# SCH_starseven_2025-07-26.net
KiCad netlist of a schematic drawn in EasyEDA
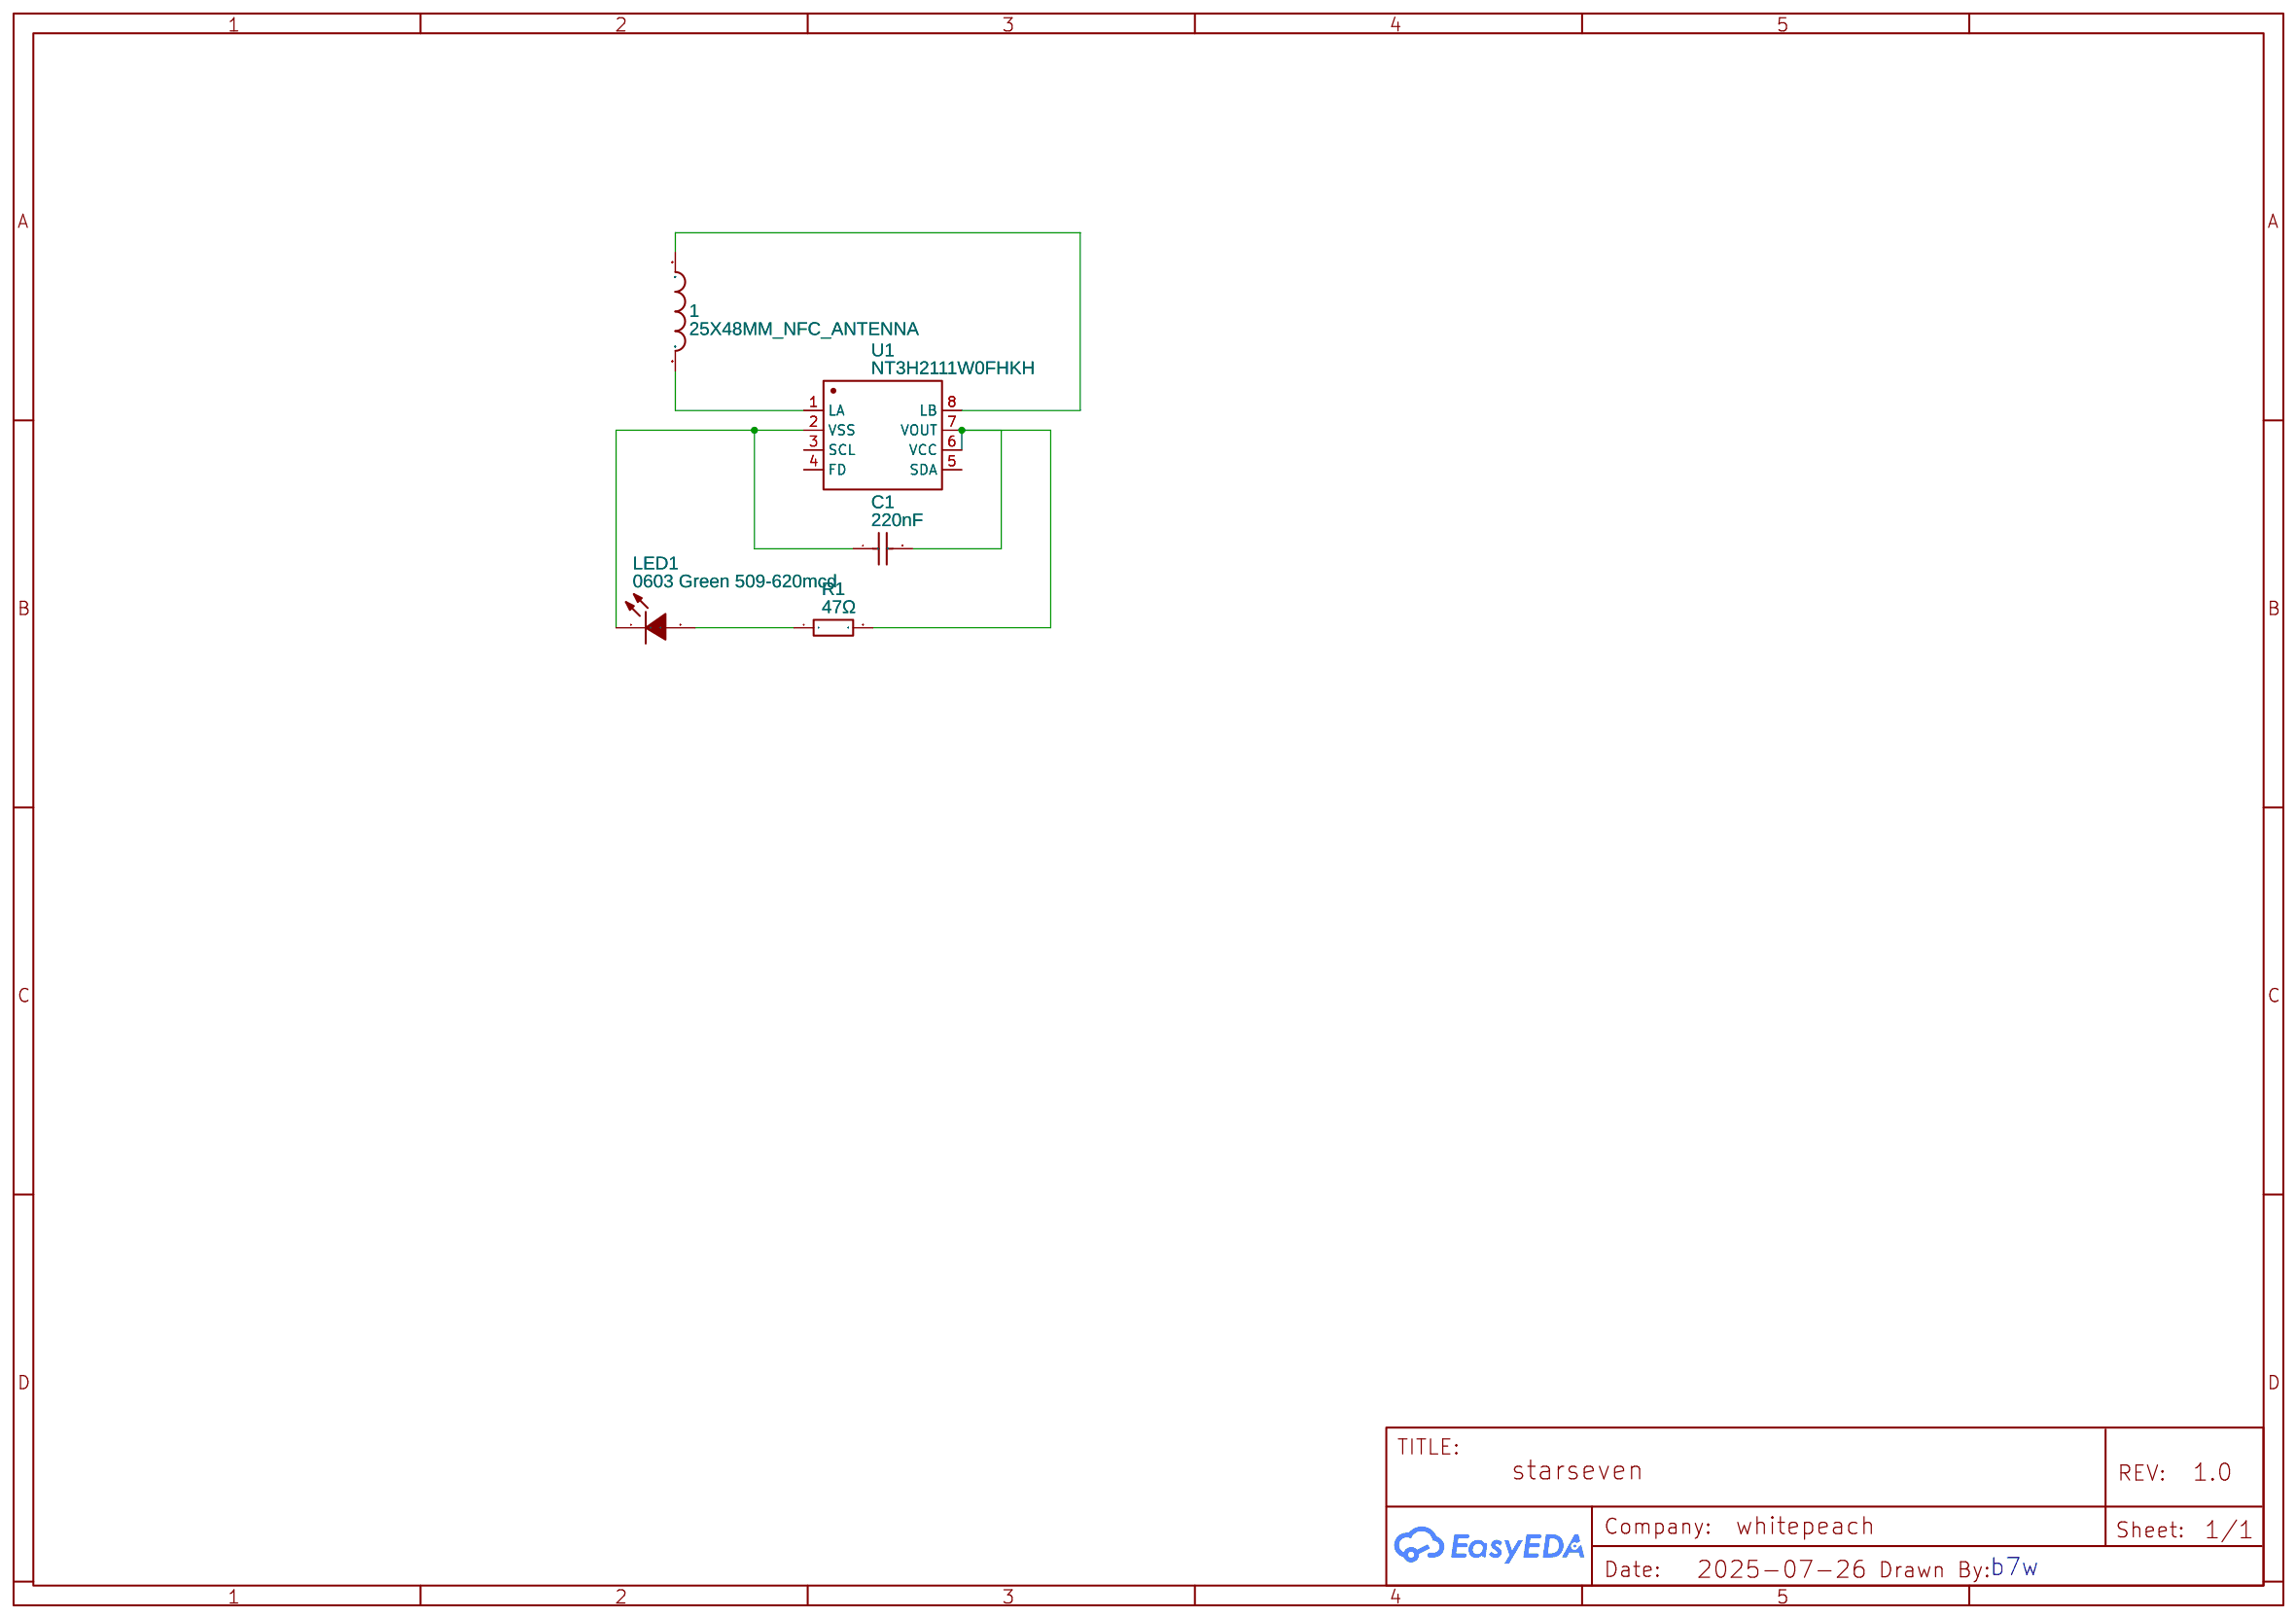
[diagram p0: schematic sheet]

(export (version "E")
  (design (tool "Eeschema 10.0.6"))
  (components
    (comp (ref "1") (value "25X48MM_NFC_ANTENNA") (libsource (lib "") (part "25X48MM_NFC_ANTENNA")))
    (comp (ref "C1")
      (value "220nF")
      (fields
        (field (name "Manufacturer Part") "CL10B224KA8NNNC")
        (field (name "Manufacturer") "SAMSUNG(三星)")
      )
      (libsource (lib "") (part "CL10B224KA8NNNC"))
    )
    (comp (ref "LED1")
      (value "0603 Green 509-620mcd")
      (fields (field (name "Manufacturer Part") "KT-0603G") (field (name "Manufacturer") "KENTO"))
      (libsource (lib "") (part "0603 Green 509-620mcd"))
    )
    (comp (ref "R1")
      (value "47Ω")
      (fields
        (field (name "Manufacturer Part") "0603WAF470JT5E")
        (field (name "Manufacturer") "UNI-ROYAL(厚声)")
      )
      (libsource (lib "") (part "0603WAF470JT5E"))
    )
    (comp (ref "U1")
      (value "NT3H2111W0FHKH")
      (fields (field (name "Manufacturer") "NXP(恩智浦)"))
      (libsource (lib "") (part "NT3H2111W0FHKH"))
    )
  )
  (nets
    (net (code "1") (name "Net-(LED1-A)") (class "Default")
      (node (ref "LED1") (pin "2") (pinfunction "A_2") (pintype "unspecified"))
      (node (ref "R1") (pin "1") (pinfunction "1_1") (pintype "input"))
    )
    (net (code "2") (name "Net-(LED1-K)") (class "Default")
      (node (ref "C1") (pin "1") (pinfunction "1_1") (pintype "input"))
      (node (ref "LED1") (pin "1") (pinfunction "K_1") (pintype "unspecified"))
      (node (ref "U1") (pin "2") (pinfunction "VSS_2") (pintype "unspecified"))
    )
    (net (code "3") (name "Net-(U1-LA)") (class "Default")
      (node (ref "1") (pin "P$2") (pinfunction "P$2_P$2") (pintype "bidirectional"))
      (node (ref "U1") (pin "1") (pinfunction "LA_1") (pintype "unspecified"))
    )
    (net (code "4") (name "Net-(U1-LB)") (class "Default")
      (node (ref "1") (pin "P$1") (pinfunction "P$1_P$1") (pintype "bidirectional"))
      (node (ref "U1") (pin "8") (pinfunction "LB_8") (pintype "unspecified"))
    )
    (net (code "5") (name "Net-(U1-VCC)") (class "Default")
      (node (ref "C1") (pin "2") (pinfunction "2_2") (pintype "input"))
      (node (ref "R1") (pin "2") (pinfunction "2_2") (pintype "input"))
      (node (ref "U1") (pin "6") (pinfunction "VCC_6") (pintype "unspecified"))
      (node (ref "U1") (pin "7") (pinfunction "VOUT_7") (pintype "unspecified"))
    )
    (net (code "6") (name "unconnected-(U1-FD-Pad4)") (class "Default")
      (node (ref "U1") (pin "4") (pinfunction "FD_4") (pintype "unspecified"))
    )
    (net (code "7") (name "unconnected-(U1-SCL-Pad3)") (class "Default")
      (node (ref "U1") (pin "3") (pinfunction "SCL_3") (pintype "unspecified"))
    )
    (net (code "8") (name "unconnected-(U1-SDA-Pad5)") (class "Default")
      (node (ref "U1") (pin "5") (pinfunction "SDA_5") (pintype "unspecified"))
    )
  )
)
